# Controlador_PID_Analogico.net
KiCad netlist of a schematic drawn in EAGLE
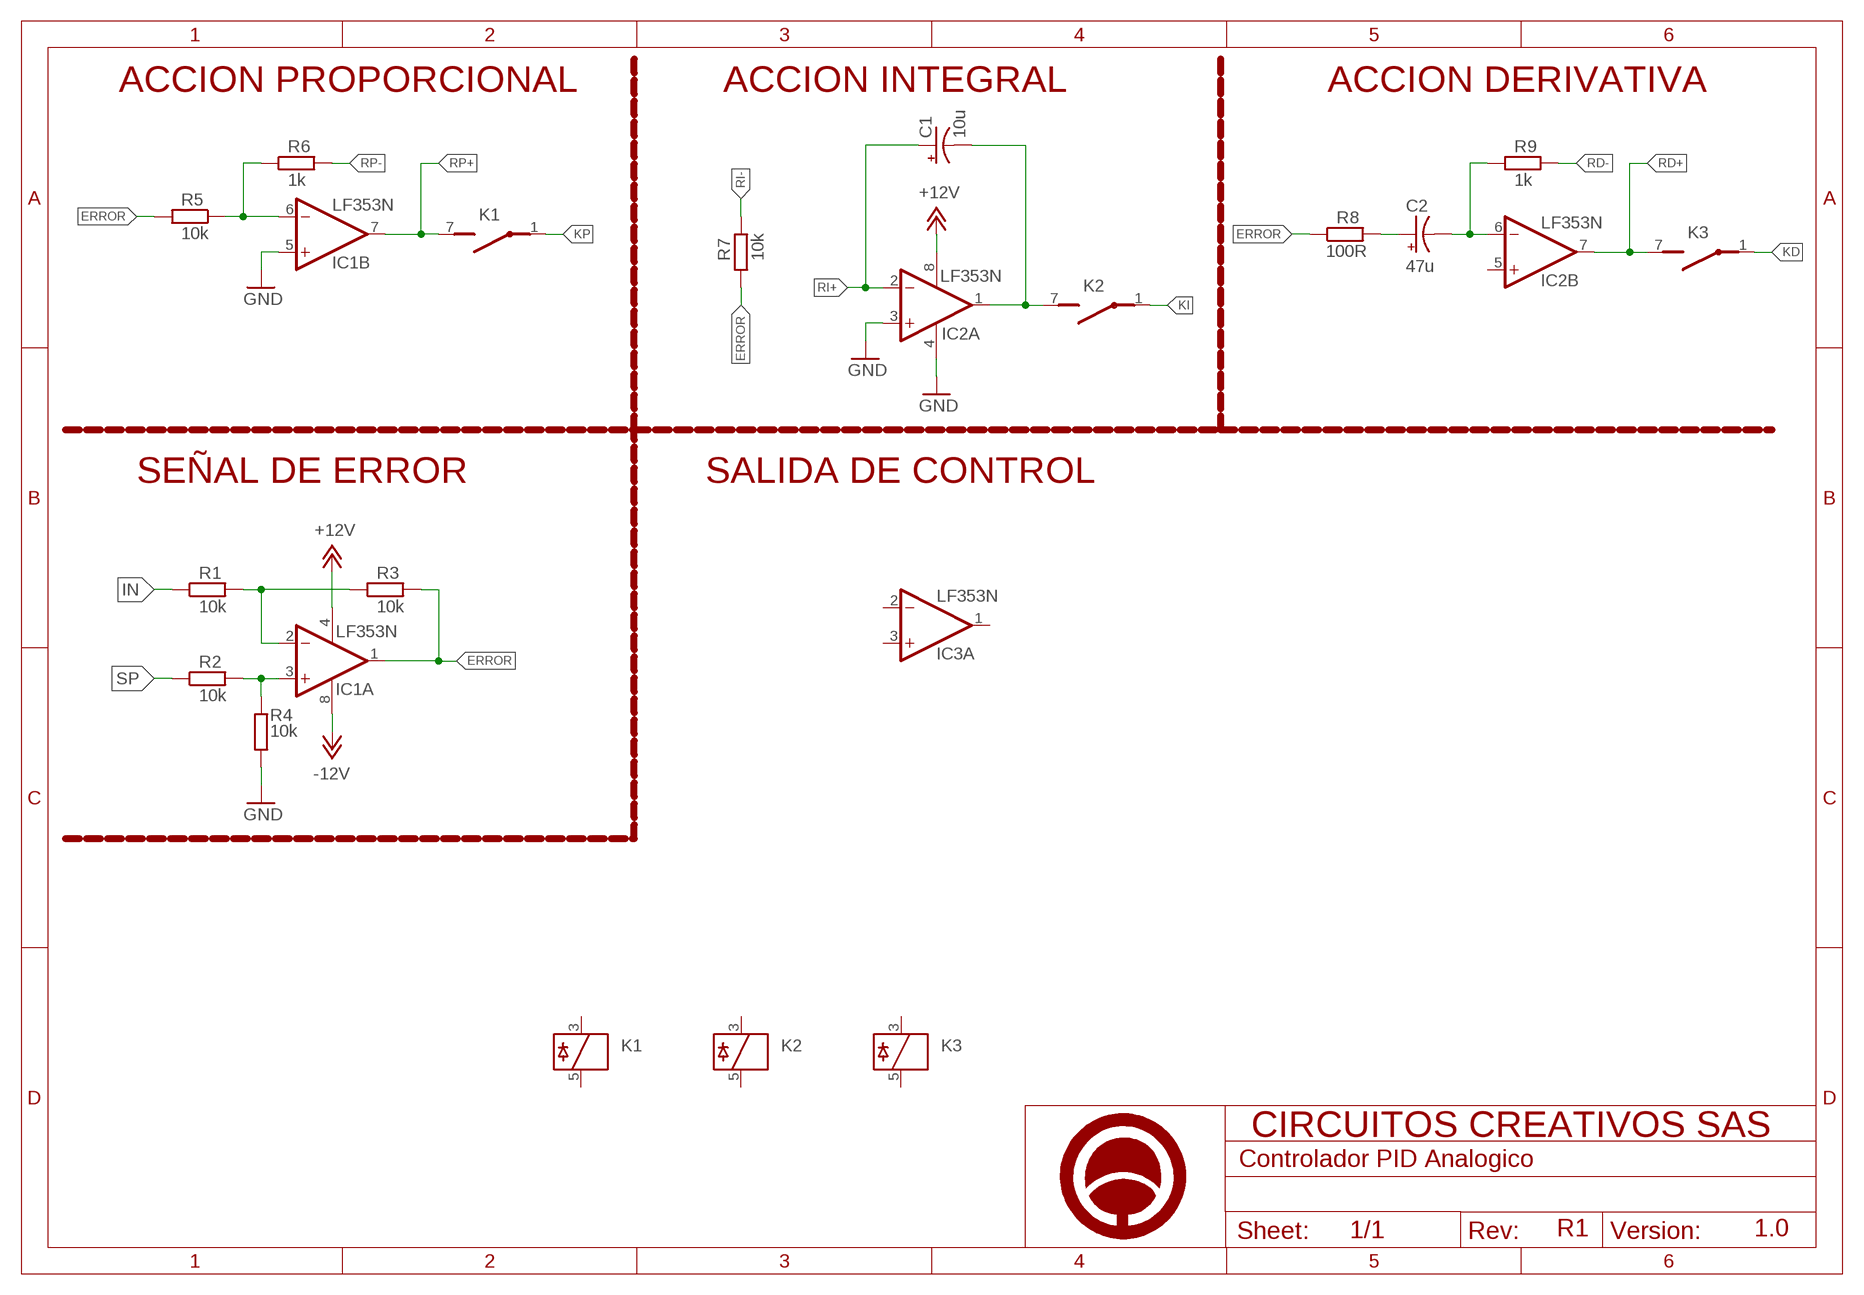
[diagram p0: schematic, sheet 1]

(export (version "E")
  (design (tool "Eeschema 10.0.6"))
  (components
    (comp (ref "C1")
      (value "10u")
      (footprint "eagle-import:E2,5-6E")
      (libsource (lib "eagle-import") (part "CPOL-USE2,5-6E"))
    )
    (comp (ref "C2")
      (value "47u")
      (footprint "eagle-import:E2,5-6E")
      (libsource (lib "eagle-import") (part "CPOL-USE2,5-6E"))
    )
    (comp (ref "IC1")
      (value "LF353N")
      (footprint "eagle-import:DIL08")
      (libsource (lib "eagle-import") (part "LF353N"))
    )
    (comp (ref "IC2")
      (value "LF353N")
      (footprint "eagle-import:DIL08")
      (libsource (lib "eagle-import") (part "LF353N"))
    )
    (comp (ref "IC3")
      (value "LF353N")
      (footprint "eagle-import:DIL08")
      (libsource (lib "eagle-import") (part "LF353N"))
    )
    (comp (ref "K1")
      (value "35701331")
      (footprint "eagle-import:REED")
      (libsource (lib "eagle-import") (part "35701331"))
    )
    (comp (ref "K2")
      (value "35701331")
      (footprint "eagle-import:REED")
      (libsource (lib "eagle-import") (part "35701331"))
    )
    (comp (ref "K3")
      (value "35701331")
      (footprint "eagle-import:REED")
      (libsource (lib "eagle-import") (part "35701331"))
    )
    (comp (ref "R1")
      (value "10k")
      (footprint "eagle-import:0204_7")
      (libsource (lib "eagle-import") (part "R-EU_0204/7"))
    )
    (comp (ref "R2")
      (value "10k")
      (footprint "eagle-import:0204_7")
      (libsource (lib "eagle-import") (part "R-EU_0204/7"))
    )
    (comp (ref "R3")
      (value "10k")
      (footprint "eagle-import:0204_7")
      (libsource (lib "eagle-import") (part "R-EU_0204/7"))
    )
    (comp (ref "R4")
      (value "10k")
      (footprint "eagle-import:0204_7")
      (libsource (lib "eagle-import") (part "R-EU_0204/7"))
    )
    (comp (ref "R5")
      (value "10k")
      (footprint "eagle-import:0204_7")
      (libsource (lib "eagle-import") (part "R-EU_0204/7"))
    )
    (comp (ref "R6")
      (value "1k")
      (footprint "eagle-import:0204_7")
      (libsource (lib "eagle-import") (part "R-EU_0204/7"))
    )
    (comp (ref "R7")
      (value "10k")
      (footprint "eagle-import:0204_7")
      (libsource (lib "eagle-import") (part "R-EU_0204/7"))
    )
    (comp (ref "R8")
      (value "100R")
      (footprint "eagle-import:0204_7")
      (libsource (lib "eagle-import") (part "R-EU_0204/7"))
    )
    (comp (ref "R9")
      (value "1k")
      (footprint "eagle-import:0204_7")
      (libsource (lib "eagle-import") (part "R-EU_0204/7"))
    )
    (comp (ref "U$1")
      (value "A4_HORIZONTAL")
      (footprint "eagle-import:LOGO")
      (libsource (lib "eagle-import") (part "A4_HORIZONTAL"))
    )
  )
  (nets
    (net (code "1") (name "+12V") (class "Default")
      (node (ref "IC1") (pin "4") (pinfunction "V-_4") (pintype "power_in"))
      (node (ref "IC2") (pin "8") (pinfunction "V+_8") (pintype "power_in"))
    )
    (net (code "2") (name "-12V") (class "Default")
      (node (ref "IC1") (pin "8") (pinfunction "V+_8") (pintype "power_in"))
    )
    (net (code "3") (name "ERROR") (class "Default")
      (node (ref "IC1") (pin "1") (pinfunction "OUT_1") (pintype "output"))
      (node (ref "R3") (pin "2") (pinfunction "2_2") (pintype "passive"))
      (node (ref "R5") (pin "2") (pinfunction "2_2") (pintype "passive"))
      (node (ref "R7") (pin "2") (pinfunction "2_2") (pintype "passive"))
      (node (ref "R8") (pin "1") (pinfunction "1_1") (pintype "passive"))
    )
    (net (code "4") (name "GND") (class "Default")
      (node (ref "IC1") (pin "5") (pinfunction "+IN_5") (pintype "input"))
      (node (ref "IC2") (pin "3") (pinfunction "+IN_3") (pintype "input"))
      (node (ref "IC2") (pin "4") (pinfunction "V-_4") (pintype "power_in"))
      (node (ref "R4") (pin "2") (pinfunction "2_2") (pintype "passive"))
    )
    (net (code "5") (name "IN") (class "Default")
      (node (ref "R1") (pin "1") (pinfunction "1_1") (pintype "passive"))
    )
    (net (code "6") (name "KD") (class "Default")
      (node (ref "K3") (pin "1") (pinfunction "P_1") (pintype "passive"))
    )
    (net (code "7") (name "KI") (class "Default")
      (node (ref "K2") (pin "1") (pinfunction "P_1") (pintype "passive"))
    )
    (net (code "8") (name "KP") (class "Default")
      (node (ref "K1") (pin "1") (pinfunction "P_1") (pintype "passive"))
    )
    (net (code "9") (name "Net-(C2-Pad+)") (class "Default")
      (node (ref "C2") (pin "+") (pinfunction "+_+") (pintype "passive"))
      (node (ref "R8") (pin "2") (pinfunction "2_2") (pintype "passive"))
    )
    (net (code "10") (name "Net-(IC1A-+IN)") (class "Default")
      (node (ref "IC1") (pin "3") (pinfunction "+IN_3") (pintype "input"))
      (node (ref "R2") (pin "2") (pinfunction "2_2") (pintype "passive"))
      (node (ref "R4") (pin "1") (pinfunction "1_1") (pintype "passive"))
    )
    (net (code "11") (name "Net-(IC1A--IN)") (class "Default")
      (node (ref "IC1") (pin "2") (pinfunction "-IN_2") (pintype "input"))
      (node (ref "R1") (pin "2") (pinfunction "2_2") (pintype "passive"))
      (node (ref "R3") (pin "1") (pinfunction "1_1") (pintype "passive"))
    )
    (net (code "12") (name "Net-(IC1B--IN)") (class "Default")
      (node (ref "IC1") (pin "6") (pinfunction "-IN_6") (pintype "input"))
      (node (ref "R5") (pin "1") (pinfunction "1_1") (pintype "passive"))
      (node (ref "R6") (pin "1") (pinfunction "1_1") (pintype "passive"))
    )
    (net (code "13") (name "Net-(IC2A-OUT)") (class "Default")
      (node (ref "C1") (pin "-") (pinfunction "-_-") (pintype "passive"))
      (node (ref "IC2") (pin "1") (pinfunction "OUT_1") (pintype "output"))
      (node (ref "K2") (pin "7") (pinfunction "S_7") (pintype "passive"))
    )
    (net (code "14") (name "Net-(IC2B--IN)") (class "Default")
      (node (ref "C2") (pin "-") (pinfunction "-_-") (pintype "passive"))
      (node (ref "IC2") (pin "6") (pinfunction "-IN_6") (pintype "input"))
      (node (ref "R9") (pin "1") (pinfunction "1_1") (pintype "passive"))
    )
    (net (code "15") (name "RD+") (class "Default")
      (node (ref "IC2") (pin "7") (pinfunction "OUT_7") (pintype "output"))
      (node (ref "K3") (pin "7") (pinfunction "S_7") (pintype "passive"))
    )
    (net (code "16") (name "RD-") (class "Default")
      (node (ref "R9") (pin "2") (pinfunction "2_2") (pintype "passive"))
    )
    (net (code "17") (name "RI+") (class "Default")
      (node (ref "C1") (pin "+") (pinfunction "+_+") (pintype "passive"))
      (node (ref "IC2") (pin "2") (pinfunction "-IN_2") (pintype "input"))
    )
    (net (code "18") (name "RI-") (class "Default")
      (node (ref "R7") (pin "1") (pinfunction "1_1") (pintype "passive"))
    )
    (net (code "19") (name "RP+") (class "Default")
      (node (ref "IC1") (pin "7") (pinfunction "OUT_7") (pintype "output"))
      (node (ref "K1") (pin "7") (pinfunction "S_7") (pintype "passive"))
    )
    (net (code "20") (name "RP-") (class "Default")
      (node (ref "R6") (pin "2") (pinfunction "2_2") (pintype "passive"))
    )
    (net (code "21") (name "SP") (class "Default")
      (node (ref "R2") (pin "1") (pinfunction "1_1") (pintype "passive"))
    )
    (net (code "22") (name "unconnected-(IC2B-+IN-Pad5)") (class "Default")
      (node (ref "IC2") (pin "5") (pinfunction "+IN_5") (pintype "input"))
    )
    (net (code "23") (name "unconnected-(IC3A-+IN-Pad3)") (class "Default")
      (node (ref "IC3") (pin "3") (pinfunction "+IN_3") (pintype "input"))
    )
    (net (code "24") (name "unconnected-(IC3A--IN-Pad2)") (class "Default")
      (node (ref "IC3") (pin "2") (pinfunction "-IN_2") (pintype "input"))
    )
    (net (code "25") (name "unconnected-(IC3A-OUT-Pad1)") (class "Default")
      (node (ref "IC3") (pin "1") (pinfunction "OUT_1") (pintype "output"))
    )
    (net (code "26") (name "unconnected-(K1-Pad3)") (class "Default")
      (node (ref "K1") (pin "3") (pinfunction "3_3") (pintype "passive"))
    )
    (net (code "27") (name "unconnected-(K1-Pad5)") (class "Default")
      (node (ref "K1") (pin "5") (pinfunction "5_5") (pintype "passive"))
    )
    (net (code "28") (name "unconnected-(K2-Pad3)") (class "Default")
      (node (ref "K2") (pin "3") (pinfunction "3_3") (pintype "passive"))
    )
    (net (code "29") (name "unconnected-(K2-Pad5)") (class "Default")
      (node (ref "K2") (pin "5") (pinfunction "5_5") (pintype "passive"))
    )
    (net (code "30") (name "unconnected-(K3-Pad3)") (class "Default")
      (node (ref "K3") (pin "3") (pinfunction "3_3") (pintype "passive"))
    )
    (net (code "31") (name "unconnected-(K3-Pad5)") (class "Default")
      (node (ref "K3") (pin "5") (pinfunction "5_5") (pintype "passive"))
    )
  )
)
